# FPGA_SLM.net
KiCad netlist of a schematic drawn in Altium Designer
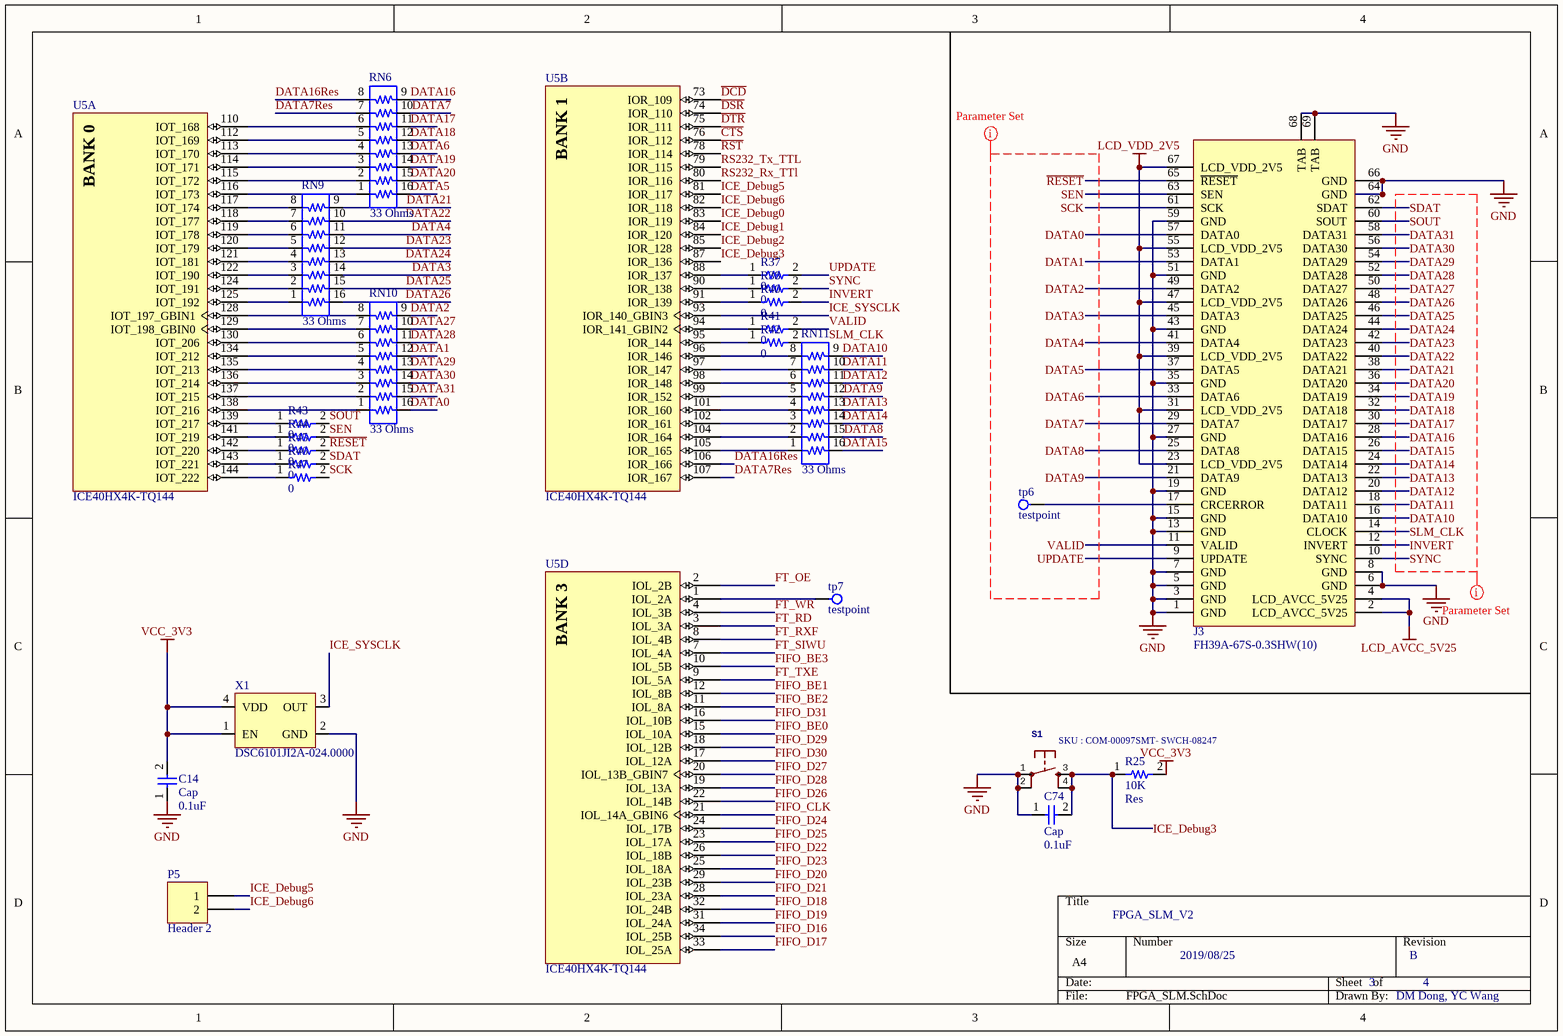
[diagram p0: FPGA_SLM.SchDoc]

(export (version "E")
  (design (tool "Eeschema 10.0.6"))
  (components
    (comp (ref "C14")
      (value "0.1uF")
      (footprint "Cap_0.1uF")
      (description "Multilayer Ceramic Capacitors MLCC - SMD/SMT 0.1uF 10% 50V AEC-Q200")
      (fields
        (field (name "COMPONENT NAME") "Cap")
        (field (name "Comment") "AC0603KRX7R9BB104")
        (field (name "CREATED BY") "Daoming Dong")
      )
      (libsource (lib "USB_FPGA_SLM_v1") (part "Cap_0.1uF"))
    )
    (comp (ref "C74")
      (value "0.1uF")
      (footprint "Cap_0.1uF")
      (description "Multilayer Ceramic Capacitors MLCC - SMD/SMT 0.1uF 10% 50V AEC-Q200")
      (fields
        (field (name "COMPONENT NAME") "Cap")
        (field (name "Comment") "AC0603KRX7R9BB104")
        (field (name "CREATED BY") "Daoming Dong")
      )
      (libsource (lib "USB_FPGA_SLM_v1") (part "Cap_0.1uF"))
    )
    (comp (ref "J3")
      (value "FH39A-67S-0.3SHW(10)")
      (footprint "Hirose_connector")
      (description "FFC & FPC Connectors FPC ZIF CONN 67 POS SMT HORZ MNT")
      (fields (field (name "CREATED BY") "Daoming Dong"))
      (libsource (lib "USB_FPGA_SLM_v1") (part "FH39A-67S-0.3SHW(10)"))
    )
    (comp (ref "P5")
      (value "Header 2")
      (footprint "HDR1X2")
      (description "Header, 2-Pin")
      (fields (field (name "PUBLISHER") "Altium Limited"))
      (libsource (lib "Miscellaneous Connectors") (part "Header 2"))
    )
    (comp (ref "R25")
      (value "10K")
      (footprint "RES_10K")
      (description "Thin Film Resistors - SMD 10K ohm 0.05% 50 ppm High-Precision")
      (fields
        (field (name "COMPONENT NAME") "Res")
        (field (name "Comment") "RT0603WRE0710KL")
        (field (name "CREATED BY") "Daoming Dong")
      )
      (libsource (lib "USB_FPGA_SLM_v1") (part "Res_10K"))
    )
    (comp (ref "R37")
      (value "0")
      (footprint "RES_0")
      (description "Thick Film Resistors - SMD 1/10Watt 0ohms Commercial Use")
      (fields (field (name "Comment") "CRCW06030000Z0EAC") (field (name "CREATED BY") "Daoming Dong"))
      (libsource (lib "USB_FPGA_SLM_v1") (part "Res_0"))
    )
    (comp (ref "R38")
      (value "0")
      (footprint "RES_0")
      (description "Thick Film Resistors - SMD 1/10Watt 0ohms Commercial Use")
      (fields (field (name "Comment") "CRCW06030000Z0EAC") (field (name "CREATED BY") "Daoming Dong"))
      (libsource (lib "USB_FPGA_SLM_v1") (part "Res_0"))
    )
    (comp (ref "R40")
      (value "0")
      (footprint "RES_0")
      (description "Thick Film Resistors - SMD 1/10Watt 0ohms Commercial Use")
      (fields (field (name "Comment") "CRCW06030000Z0EAC") (field (name "CREATED BY") "Daoming Dong"))
      (libsource (lib "USB_FPGA_SLM_v1") (part "Res_0"))
    )
    (comp (ref "R41")
      (value "0")
      (footprint "RES_0")
      (description "Thick Film Resistors - SMD 1/10Watt 0ohms Commercial Use")
      (fields (field (name "Comment") "CRCW06030000Z0EAC") (field (name "CREATED BY") "Daoming Dong"))
      (libsource (lib "USB_FPGA_SLM_v1") (part "Res_0"))
    )
    (comp (ref "R42")
      (value "0")
      (footprint "RES_0")
      (description "Thick Film Resistors - SMD 1/10Watt 0ohms Commercial Use")
      (fields (field (name "Comment") "CRCW06030000Z0EAC") (field (name "CREATED BY") "Daoming Dong"))
      (libsource (lib "USB_FPGA_SLM_v1") (part "Res_0"))
    )
    (comp (ref "R43")
      (value "0")
      (footprint "RES_0")
      (description "Thick Film Resistors - SMD 1/10Watt 0ohms Commercial Use")
      (fields (field (name "Comment") "CRCW06030000Z0EAC") (field (name "CREATED BY") "Daoming Dong"))
      (libsource (lib "USB_FPGA_SLM_v1") (part "Res_0"))
    )
    (comp (ref "R44")
      (value "0")
      (footprint "RES_0")
      (description "Thick Film Resistors - SMD 1/10Watt 0ohms Commercial Use")
      (fields (field (name "Comment") "CRCW06030000Z0EAC") (field (name "CREATED BY") "Daoming Dong"))
      (libsource (lib "USB_FPGA_SLM_v1") (part "Res_0"))
    )
    (comp (ref "R45")
      (value "0")
      (footprint "RES_0")
      (description "Thick Film Resistors - SMD 1/10Watt 0ohms Commercial Use")
      (fields (field (name "Comment") "CRCW06030000Z0EAC") (field (name "CREATED BY") "Daoming Dong"))
      (libsource (lib "USB_FPGA_SLM_v1") (part "Res_0"))
    )
    (comp (ref "R46")
      (value "0")
      (footprint "RES_0")
      (description "Thick Film Resistors - SMD 1/10Watt 0ohms Commercial Use")
      (fields (field (name "Comment") "CRCW06030000Z0EAC") (field (name "CREATED BY") "Daoming Dong"))
      (libsource (lib "USB_FPGA_SLM_v1") (part "Res_0"))
    )
    (comp (ref "R47")
      (value "0")
      (footprint "RES_0")
      (description "Thick Film Resistors - SMD 1/10Watt 0ohms Commercial Use")
      (fields (field (name "Comment") "CRCW06030000Z0EAC") (field (name "CREATED BY") "Daoming Dong"))
      (libsource (lib "USB_FPGA_SLM_v1") (part "Res_0"))
    )
    (comp (ref "RN6")
      (value "33 Ohms")
      (footprint "ResArray_0")
      (description "Resistor Networks & Arrays 33 OHM 5%")
      (fields (field (name "Comment") "EXB-2HV330JV"))
      (libsource (lib "USB_FPGA_SLM_v1") (part "ResArray"))
    )
    (comp (ref "RN9")
      (value "33 Ohms")
      (footprint "ResArray_0")
      (description "Resistor Networks & Arrays 33 OHM 5%")
      (fields (field (name "Comment") "EXB-2HV330JV"))
      (libsource (lib "USB_FPGA_SLM_v1") (part "ResArray"))
    )
    (comp (ref "RN10")
      (value "33 Ohms")
      (footprint "ResArray_0")
      (description "Resistor Networks & Arrays 33 OHM 5%")
      (fields (field (name "Comment") "EXB-2HV330JV"))
      (libsource (lib "USB_FPGA_SLM_v1") (part "ResArray"))
    )
    (comp (ref "RN11")
      (value "33 Ohms")
      (footprint "ResArray_0")
      (description "Resistor Networks & Arrays 33 OHM 5%")
      (fields (field (name "Comment") "EXB-2HV330JV"))
      (libsource (lib "USB_FPGA_SLM_v1") (part "ResArray"))
    )
    (comp (ref "S1")
      (value "SKU : COM-00097SMT- SWCH-08247")
      (footprint "TACTILE-PTH")
      (libsource (lib "SparkFun-Electromechanical") (part "TAC_SWITCHPTH"))
    )
    (comp (ref "tp6")
      (value "testpoint")
      (footprint "testpoint")
      (description "Testpoint for testing voltage")
      (fields (field (name "CREATED BY") "Daoming Dong"))
      (libsource (lib "USB_FPGA_SLM_v1") (part "Testpoint"))
    )
    (comp (ref "tp7")
      (value "testpoint")
      (footprint "testpoint")
      (description "Testpoint for testing voltage")
      (fields (field (name "CREATED BY") "Daoming Dong"))
      (libsource (lib "USB_FPGA_SLM_v1") (part "Testpoint"))
    )
    (comp (ref "U5")
      (value "ICE40HX4K-TQ144")
      (footprint "LATC-TQFP-144_L")
      (fields (field (name "MANUFACTURER") "Lattice Semiconductor"))
      (libsource (lib "Lattice iCE40") (part "ICE40HX4K-TQ144"))
    )
    (comp (ref "X1")
      (value "DSC6101JI2A-024.0000")
      (footprint "24MHzOscillator")
      (description "Standard Clock Oscillators MEMS Oscillator, Ultra Low Power, LVCMOS, -40C-85C, 25ppm, 2.5x2.0mm")
      (fields (field (name "CREATED BY") "Daoming Dong"))
      (libsource (lib "USB_FPGA_SLM_v1") (part "24MHzOscillator"))
    )
  )
  (nets
    (net (code "1") (name "/DATA0") (class "Default")
      (node (ref "J3") (pin "57") (pinfunction "DATA0_57") (pintype "passive"))
      (node (ref "RN10") (pin "16") (pinfunction "16_16") (pintype "passive"))
    )
    (net (code "2") (name "/DATA1") (class "Default")
      (node (ref "J3") (pin "53") (pinfunction "DATA1_53") (pintype "passive"))
      (node (ref "RN10") (pin "12") (pinfunction "12_12") (pintype "passive"))
    )
    (net (code "3") (name "/DATA2") (class "Default")
      (node (ref "J3") (pin "49") (pinfunction "DATA2_49") (pintype "passive"))
      (node (ref "RN10") (pin "9") (pinfunction "9_9") (pintype "passive"))
    )
    (net (code "4") (name "/DATA3") (class "Default")
      (node (ref "J3") (pin "45") (pinfunction "DATA3_45") (pintype "passive"))
      (node (ref "RN9") (pin "14") (pinfunction "14_14") (pintype "passive"))
    )
    (net (code "5") (name "/DATA4") (class "Default")
      (node (ref "J3") (pin "41") (pinfunction "DATA4_41") (pintype "passive"))
      (node (ref "RN9") (pin "11") (pinfunction "11_11") (pintype "passive"))
    )
    (net (code "6") (name "/DATA5") (class "Default")
      (node (ref "J3") (pin "37") (pinfunction "DATA5_37") (pintype "passive"))
      (node (ref "RN6") (pin "16") (pinfunction "16_16") (pintype "passive"))
    )
    (net (code "7") (name "/DATA6") (class "Default")
      (node (ref "J3") (pin "33") (pinfunction "DATA6_33") (pintype "passive"))
      (node (ref "RN6") (pin "13") (pinfunction "13_13") (pintype "passive"))
    )
    (net (code "8") (name "/DATA7") (class "Default")
      (node (ref "J3") (pin "29") (pinfunction "DATA7_29") (pintype "passive"))
      (node (ref "RN6") (pin "10") (pinfunction "10_10") (pintype "passive"))
    )
    (net (code "9") (name "/DATA7Res") (class "Default")
      (node (ref "RN6") (pin "7") (pinfunction "7_7") (pintype "passive"))
      (node (ref "U5") (pin "107") (pinfunction "IOR_167_107") (pintype "bidirectional"))
    )
    (net (code "10") (name "/DATA8") (class "Default")
      (node (ref "J3") (pin "25") (pinfunction "DATA8_25") (pintype "passive"))
      (node (ref "RN11") (pin "15") (pinfunction "15_15") (pintype "passive"))
    )
    (net (code "11") (name "/DATA9") (class "Default")
      (node (ref "J3") (pin "21") (pinfunction "DATA9_21") (pintype "passive"))
      (node (ref "RN11") (pin "12") (pinfunction "12_12") (pintype "passive"))
    )
    (net (code "12") (name "/DATA10") (class "Default")
      (node (ref "J3") (pin "16") (pinfunction "DATA10_16") (pintype "passive"))
      (node (ref "RN11") (pin "9") (pinfunction "9_9") (pintype "passive"))
    )
    (net (code "13") (name "/DATA11") (class "Default")
      (node (ref "J3") (pin "18") (pinfunction "DATA11_18") (pintype "passive"))
      (node (ref "RN11") (pin "10") (pinfunction "10_10") (pintype "passive"))
    )
    (net (code "14") (name "/DATA12") (class "Default")
      (node (ref "J3") (pin "20") (pinfunction "DATA12_20") (pintype "passive"))
      (node (ref "RN11") (pin "11") (pinfunction "11_11") (pintype "passive"))
    )
    (net (code "15") (name "/DATA13") (class "Default")
      (node (ref "J3") (pin "22") (pinfunction "DATA13_22") (pintype "passive"))
      (node (ref "RN11") (pin "13") (pinfunction "13_13") (pintype "passive"))
    )
    (net (code "16") (name "/DATA14") (class "Default")
      (node (ref "J3") (pin "24") (pinfunction "DATA14_24") (pintype "passive"))
      (node (ref "RN11") (pin "14") (pinfunction "14_14") (pintype "passive"))
    )
    (net (code "17") (name "/DATA15") (class "Default")
      (node (ref "J3") (pin "26") (pinfunction "DATA15_26") (pintype "passive"))
      (node (ref "RN11") (pin "16") (pinfunction "16_16") (pintype "passive"))
    )
    (net (code "18") (name "/DATA16") (class "Default")
      (node (ref "J3") (pin "28") (pinfunction "DATA16_28") (pintype "passive"))
      (node (ref "RN6") (pin "9") (pinfunction "9_9") (pintype "passive"))
    )
    (net (code "19") (name "/DATA16Res") (class "Default")
      (node (ref "RN6") (pin "8") (pinfunction "8_8") (pintype "passive"))
      (node (ref "U5") (pin "106") (pinfunction "IOR_166_106") (pintype "bidirectional"))
    )
    (net (code "20") (name "/DATA17") (class "Default")
      (node (ref "J3") (pin "30") (pinfunction "DATA17_30") (pintype "passive"))
      (node (ref "RN6") (pin "11") (pinfunction "11_11") (pintype "passive"))
    )
    (net (code "21") (name "/DATA18") (class "Default")
      (node (ref "J3") (pin "32") (pinfunction "DATA18_32") (pintype "passive"))
      (node (ref "RN6") (pin "12") (pinfunction "12_12") (pintype "passive"))
    )
    (net (code "22") (name "/DATA19") (class "Default")
      (node (ref "J3") (pin "34") (pinfunction "DATA19_34") (pintype "passive"))
      (node (ref "RN6") (pin "14") (pinfunction "14_14") (pintype "passive"))
    )
    (net (code "23") (name "/DATA20") (class "Default")
      (node (ref "J3") (pin "36") (pinfunction "DATA20_36") (pintype "passive"))
      (node (ref "RN6") (pin "15") (pinfunction "15_15") (pintype "passive"))
    )
    (net (code "24") (name "/DATA21") (class "Default")
      (node (ref "J3") (pin "38") (pinfunction "DATA21_38") (pintype "passive"))
      (node (ref "RN9") (pin "9") (pinfunction "9_9") (pintype "passive"))
    )
    (net (code "25") (name "/DATA22") (class "Default")
      (node (ref "J3") (pin "40") (pinfunction "DATA22_40") (pintype "passive"))
      (node (ref "RN9") (pin "10") (pinfunction "10_10") (pintype "passive"))
    )
    (net (code "26") (name "/DATA23") (class "Default")
      (node (ref "J3") (pin "42") (pinfunction "DATA23_42") (pintype "passive"))
      (node (ref "RN9") (pin "12") (pinfunction "12_12") (pintype "passive"))
    )
    (net (code "27") (name "/DATA24") (class "Default")
      (node (ref "J3") (pin "44") (pinfunction "DATA24_44") (pintype "passive"))
      (node (ref "RN9") (pin "13") (pinfunction "13_13") (pintype "passive"))
    )
    (net (code "28") (name "/DATA25") (class "Default")
      (node (ref "J3") (pin "46") (pinfunction "DATA25_46") (pintype "passive"))
      (node (ref "RN9") (pin "15") (pinfunction "15_15") (pintype "passive"))
    )
    (net (code "29") (name "/DATA26") (class "Default")
      (node (ref "J3") (pin "48") (pinfunction "DATA26_48") (pintype "passive"))
      (node (ref "RN9") (pin "16") (pinfunction "16_16") (pintype "passive"))
    )
    (net (code "30") (name "/DATA27") (class "Default")
      (node (ref "J3") (pin "50") (pinfunction "DATA27_50") (pintype "passive"))
      (node (ref "RN10") (pin "10") (pinfunction "10_10") (pintype "passive"))
    )
    (net (code "31") (name "/DATA28") (class "Default")
      (node (ref "J3") (pin "52") (pinfunction "DATA28_52") (pintype "passive"))
      (node (ref "RN10") (pin "11") (pinfunction "11_11") (pintype "passive"))
    )
    (net (code "32") (name "/DATA29") (class "Default")
      (node (ref "J3") (pin "54") (pinfunction "DATA29_54") (pintype "passive"))
      (node (ref "RN10") (pin "13") (pinfunction "13_13") (pintype "passive"))
    )
    (net (code "33") (name "/DATA30") (class "Default")
      (node (ref "J3") (pin "56") (pinfunction "DATA30_56") (pintype "passive"))
      (node (ref "RN10") (pin "14") (pinfunction "14_14") (pintype "passive"))
    )
    (net (code "34") (name "/DATA31") (class "Default")
      (node (ref "J3") (pin "58") (pinfunction "DATA31_58") (pintype "passive"))
      (node (ref "RN10") (pin "15") (pinfunction "15_15") (pintype "passive"))
    )
    (net (code "35") (name "/FIFO_BE0") (class "Default")
      (node (ref "U5") (pin "15") (pinfunction "IOL_10A_15") (pintype "bidirectional"))
    )
    (net (code "36") (name "/FIFO_BE1") (class "Default")
      (node (ref "U5") (pin "12") (pinfunction "IOL_8B_12") (pintype "bidirectional"))
    )
    (net (code "37") (name "/FIFO_BE2") (class "Default")
      (node (ref "U5") (pin "11") (pinfunction "IOL_8A_11") (pintype "bidirectional"))
    )
    (net (code "38") (name "/FIFO_BE3") (class "Default")
      (node (ref "U5") (pin "10") (pinfunction "IOL_5B_10") (pintype "bidirectional"))
    )
    (net (code "39") (name "/FIFO_CLK") (class "Default")
      (node (ref "U5") (pin "21") (pinfunction "IOL_14A_GBIN6_21") (pintype "bidirectional"))
    )
    (net (code "40") (name "/FIFO_D16") (class "Default")
      (node (ref "U5") (pin "34") (pinfunction "IOL_25B_34") (pintype "bidirectional"))
    )
    (net (code "41") (name "/FIFO_D17") (class "Default")
      (node (ref "U5") (pin "33") (pinfunction "IOL_25A_33") (pintype "bidirectional"))
    )
    (net (code "42") (name "/FIFO_D18") (class "Default")
      (node (ref "U5") (pin "32") (pinfunction "IOL_24B_32") (pintype "bidirectional"))
    )
    (net (code "43") (name "/FIFO_D19") (class "Default")
      (node (ref "U5") (pin "31") (pinfunction "IOL_24A_31") (pintype "bidirectional"))
    )
    (net (code "44") (name "/FIFO_D20") (class "Default")
      (node (ref "U5") (pin "29") (pinfunction "IOL_23B_29") (pintype "bidirectional"))
    )
    (net (code "45") (name "/FIFO_D21") (class "Default")
      (node (ref "U5") (pin "28") (pinfunction "IOL_23A_28") (pintype "bidirectional"))
    )
    (net (code "46") (name "/FIFO_D22") (class "Default")
      (node (ref "U5") (pin "26") (pinfunction "IOL_18B_26") (pintype "bidirectional"))
    )
    (net (code "47") (name "/FIFO_D23") (class "Default")
      (node (ref "U5") (pin "25") (pinfunction "IOL_18A_25") (pintype "bidirectional"))
    )
    (net (code "48") (name "/FIFO_D24") (class "Default")
      (node (ref "U5") (pin "24") (pinfunction "IOL_17B_24") (pintype "bidirectional"))
    )
    (net (code "49") (name "/FIFO_D25") (class "Default")
      (node (ref "U5") (pin "23") (pinfunction "IOL_17A_23") (pintype "bidirectional"))
    )
    (net (code "50") (name "/FIFO_D26") (class "Default")
      (node (ref "U5") (pin "22") (pinfunction "IOL_14B_22") (pintype "bidirectional"))
    )
    (net (code "51") (name "/FIFO_D27") (class "Default")
      (node (ref "U5") (pin "20") (pinfunction "IOL_13B_GBIN7_20") (pintype "bidirectional"))
    )
    (net (code "52") (name "/FIFO_D28") (class "Default")
      (node (ref "U5") (pin "19") (pinfunction "IOL_13A_19") (pintype "bidirectional"))
    )
    (net (code "53") (name "/FIFO_D29") (class "Default")
      (node (ref "U5") (pin "18") (pinfunction "IOL_12B_18") (pintype "bidirectional"))
    )
    (net (code "54") (name "/FIFO_D30") (class "Default")
      (node (ref "U5") (pin "17") (pinfunction "IOL_12A_17") (pintype "bidirectional"))
    )
    (net (code "55") (name "/FIFO_D31") (class "Default")
      (node (ref "U5") (pin "16") (pinfunction "IOL_10B_16") (pintype "bidirectional"))
    )
    (net (code "56") (name "/FT_OE") (class "Default")
      (node (ref "U5") (pin "2") (pinfunction "IOL_2B_2") (pintype "bidirectional"))
    )
    (net (code "57") (name "/FT_RD") (class "Default")
      (node (ref "U5") (pin "3") (pinfunction "IOL_3A_3") (pintype "bidirectional"))
    )
    (net (code "58") (name "/FT_RXF") (class "Default")
      (node (ref "U5") (pin "8") (pinfunction "IOL_4B_8") (pintype "bidirectional"))
    )
    (net (code "59") (name "/FT_SIWU") (class "Default")
      (node (ref "U5") (pin "7") (pinfunction "IOL_4A_7") (pintype "bidirectional"))
    )
    (net (code "60") (name "/FT_TXE") (class "Default")
      (node (ref "U5") (pin "9") (pinfunction "IOL_5A_9") (pintype "bidirectional"))
    )
    (net (code "61") (name "/FT_WR") (class "Default")
      (node (ref "U5") (pin "4") (pinfunction "IOL_3B_4") (pintype "bidirectional"))
    )
    (net (code "62") (name "/ICE_Debug0") (class "Default")
      (node (ref "U5") (pin "83") (pinfunction "IOR_119_83") (pintype "bidirectional"))
    )
    (net (code "63") (name "/ICE_Debug1") (class "Default")
      (node (ref "U5") (pin "84") (pinfunction "IOR_120_84") (pintype "bidirectional"))
    )
    (net (code "64") (name "/ICE_Debug2") (class "Default")
      (node (ref "U5") (pin "85") (pinfunction "IOR_128_85") (pintype "bidirectional"))
    )
    (net (code "65") (name "/ICE_Debug3") (class "Default")
      (node (ref "C74") (pin "2") (pinfunction "2_2") (pintype "passive"))
      (node (ref "R25") (pin "1") (pinfunction "1_1") (pintype "passive"))
      (node (ref "S1") (pin "3") (pinfunction "3_3") (pintype "passive"))
      (node (ref "S1") (pin "4") (pinfunction "4_4") (pintype "passive"))
      (node (ref "U5") (pin "87") (pinfunction "IOR_136_87") (pintype "bidirectional"))
    )
    (net (code "66") (name "/ICE_Debug5") (class "Default")
      (node (ref "P5") (pin "1") (pinfunction "1_1") (pintype "passive"))
      (node (ref "U5") (pin "81") (pinfunction "IOR_117_81") (pintype "bidirectional"))
    )
    (net (code "67") (name "/ICE_Debug6") (class "Default")
      (node (ref "P5") (pin "2") (pinfunction "2_2") (pintype "passive"))
      (node (ref "U5") (pin "82") (pinfunction "IOR_118_82") (pintype "bidirectional"))
    )
    (net (code "68") (name "/ICE_SYSCLK") (class "Default")
      (node (ref "U5") (pin "93") (pinfunction "IOR_140_GBIN3_93") (pintype "bidirectional"))
      (node (ref "X1") (pin "3") (pinfunction "OUT_3") (pintype "passive"))
    )
    (net (code "69") (name "/INVERT") (class "Default")
      (node (ref "J3") (pin "12") (pinfunction "INVERT_12") (pintype "passive"))
      (node (ref "R40") (pin "2") (pinfunction "2_2") (pintype "passive"))
    )
    (net (code "70") (name "/RS232_Rx_TTl") (class "Default")
      (node (ref "U5") (pin "80") (pinfunction "IOR_116_80") (pintype "bidirectional"))
    )
    (net (code "71") (name "/RS232_Tx_TTL") (class "Default")
      (node (ref "U5") (pin "79") (pinfunction "IOR_115_79") (pintype "bidirectional"))
    )
    (net (code "72") (name "/SCK") (class "Default")
      (node (ref "J3") (pin "61") (pinfunction "SCK_61") (pintype "passive"))
      (node (ref "R47") (pin "2") (pinfunction "2_2") (pintype "passive"))
    )
    (net (code "73") (name "/SDAT") (class "Default")
      (node (ref "J3") (pin "62") (pinfunction "SDAT_62") (pintype "passive"))
      (node (ref "R46") (pin "2") (pinfunction "2_2") (pintype "passive"))
    )
    (net (code "74") (name "/SEN") (class "Default")
      (node (ref "J3") (pin "63") (pinfunction "SEN_63") (pintype "passive"))
      (node (ref "R44") (pin "2") (pinfunction "2_2") (pintype "passive"))
    )
    (net (code "75") (name "/SLM_CLK") (class "Default")
      (node (ref "J3") (pin "14") (pinfunction "CLOCK_14") (pintype "passive"))
      (node (ref "R42") (pin "2") (pinfunction "2_2") (pintype "passive"))
    )
    (net (code "76") (name "/SOUT") (class "Default")
      (node (ref "J3") (pin "60") (pinfunction "SOUT_60") (pintype "passive"))
      (node (ref "R43") (pin "2") (pinfunction "2_2") (pintype "passive"))
    )
    (net (code "77") (name "/SYNC") (class "Default")
      (node (ref "J3") (pin "10") (pinfunction "SYNC_10") (pintype "passive"))
      (node (ref "R38") (pin "2") (pinfunction "2_2") (pintype "passive"))
    )
    (net (code "78") (name "/UPDATE") (class "Default")
      (node (ref "J3") (pin "9") (pinfunction "UPDATE_9") (pintype "passive"))
      (node (ref "R37") (pin "2") (pinfunction "2_2") (pintype "passive"))
    )
    (net (code "79") (name "/VALID") (class "Default")
      (node (ref "J3") (pin "11") (pinfunction "VALID_11") (pintype "passive"))
      (node (ref "R41") (pin "2") (pinfunction "2_2") (pintype "passive"))
    )
    (net (code "80") (name "/~{CTS}") (class "Default")
      (node (ref "U5") (pin "76") (pinfunction "IOR_112_76") (pintype "bidirectional"))
    )
    (net (code "81") (name "/~{DCD}") (class "Default")
      (node (ref "U5") (pin "73") (pinfunction "IOR_109_73") (pintype "bidirectional"))
    )
    (net (code "82") (name "/~{DSR}") (class "Default")
      (node (ref "U5") (pin "74") (pinfunction "IOR_110_74") (pintype "bidirectional"))
    )
    (net (code "83") (name "/~{DTR}") (class "Default")
      (node (ref "U5") (pin "75") (pinfunction "IOR_111_75") (pintype "bidirectional"))
    )
    (net (code "84") (name "/~{RESET}") (class "Default")
      (node (ref "J3") (pin "65") (pinfunction "~{RESET}_65") (pintype "passive"))
      (node (ref "R45") (pin "2") (pinfunction "2_2") (pintype "passive"))
    )
    (net (code "85") (name "/~{RST}") (class "Default")
      (node (ref "U5") (pin "78") (pinfunction "IOR_114_78") (pintype "bidirectional"))
    )
    (net (code "86") (name "GND") (class "Default")
      (node (ref "C14") (pin "1") (pinfunction "1_1") (pintype "passive"))
      (node (ref "C74") (pin "1") (pinfunction "1_1") (pintype "passive"))
      (node (ref "J3") (pin "1") (pinfunction "GND_1") (pintype "passive"))
      (node (ref "J3") (pin "13") (pinfunction "GND_13") (pintype "passive"))
      (node (ref "J3") (pin "15") (pinfunction "GND_15") (pintype "passive"))
      (node (ref "J3") (pin "19") (pinfunction "GND_19") (pintype "passive"))
      (node (ref "J3") (pin "27") (pinfunction "GND_27") (pintype "passive"))
      (node (ref "J3") (pin "3") (pinfunction "GND_3") (pintype "passive"))
      (node (ref "J3") (pin "35") (pinfunction "GND_35") (pintype "passive"))
      (node (ref "J3") (pin "43") (pinfunction "GND_43") (pintype "passive"))
      (node (ref "J3") (pin "5") (pinfunction "GND_5") (pintype "passive"))
      (node (ref "J3") (pin "51") (pinfunction "GND_51") (pintype "passive"))
      (node (ref "J3") (pin "59") (pinfunction "GND_59") (pintype "passive"))
      (node (ref "J3") (pin "6") (pinfunction "GND_6") (pintype "passive"))
      (node (ref "J3") (pin "64") (pinfunction "GND_64") (pintype "passive"))
      (node (ref "J3") (pin "66") (pinfunction "GND_66") (pintype "passive"))
      (node (ref "J3") (pin "68") (pinfunction "TAB_68") (pintype "passive"))
      (node (ref "J3") (pin "69") (pinfunction "TAB_69") (pintype "passive"))
      (node (ref "J3") (pin "7") (pinfunction "GND_7") (pintype "passive"))
      (node (ref "J3") (pin "8") (pinfunction "GND_8") (pintype "passive"))
      (node (ref "S1") (pin "1") (pinfunction "1_1") (pintype "passive"))
      (node (ref "S1") (pin "2") (pinfunction "2_2") (pintype "passive"))
      (node (ref "X1") (pin "2") (pinfunction "GND_2") (pintype "passive"))
    )
    (net (code "87") (name "LCD_AVCC_5V25") (class "Default")
      (node (ref "J3") (pin "2") (pinfunction "LCD_AVCC_5V25_2") (pintype "passive"))
      (node (ref "J3") (pin "4") (pinfunction "LCD_AVCC_5V25_4") (pintype "passive"))
    )
    (net (code "88") (name "LCD_VDD_2V5") (class "Default")
      (node (ref "J3") (pin "23") (pinfunction "LCD_VDD_2V5_23") (pintype "passive"))
      (node (ref "J3") (pin "31") (pinfunction "LCD_VDD_2V5_31") (pintype "passive"))
      (node (ref "J3") (pin "39") (pinfunction "LCD_VDD_2V5_39") (pintype "passive"))
      (node (ref "J3") (pin "47") (pinfunction "LCD_VDD_2V5_47") (pintype "passive"))
      (node (ref "J3") (pin "55") (pinfunction "LCD_VDD_2V5_55") (pintype "passive"))
      (node (ref "J3") (pin "67") (pinfunction "LCD_VDD_2V5_67") (pintype "passive"))
    )
    (net (code "89") (name "Net-(J3-CRCERROR)") (class "Default")
      (node (ref "J3") (pin "17") (pinfunction "CRCERROR_17") (pintype "passive"))
      (node (ref "tp6") (pin "1") (pinfunction "1_1") (pintype "passive"))
    )
    (net (code "90") (name "Net-(U5A-IOT_168)") (class "Default")
      (node (ref "RN6") (pin "6") (pinfunction "6_6") (pintype "passive"))
      (node (ref "U5") (pin "110") (pinfunction "IOT_168_110") (pintype "bidirectional"))
    )
    (net (code "91") (name "Net-(U5A-IOT_169)") (class "Default")
      (node (ref "RN6") (pin "5") (pinfunction "5_5") (pintype "passive"))
      (node (ref "U5") (pin "112") (pinfunction "IOT_169_112") (pintype "bidirectional"))
    )
    (net (code "92") (name "Net-(U5A-IOT_170)") (class "Default")
      (node (ref "RN6") (pin "4") (pinfunction "4_4") (pintype "passive"))
      (node (ref "U5") (pin "113") (pinfunction "IOT_170_113") (pintype "bidirectional"))
    )
    (net (code "93") (name "Net-(U5A-IOT_171)") (class "Default")
      (node (ref "RN6") (pin "3") (pinfunction "3_3") (pintype "passive"))
      (node (ref "U5") (pin "114") (pinfunction "IOT_171_114") (pintype "bidirectional"))
    )
    (net (code "94") (name "Net-(U5A-IOT_172)") (class "Default")
      (node (ref "RN6") (pin "2") (pinfunction "2_2") (pintype "passive"))
      (node (ref "U5") (pin "115") (pinfunction "IOT_172_115") (pintype "bidirectional"))
    )
    (net (code "95") (name "Net-(U5A-IOT_173)") (class "Default")
      (node (ref "RN6") (pin "1") (pinfunction "1_1") (pintype "passive"))
      (node (ref "U5") (pin "116") (pinfunction "IOT_173_116") (pintype "bidirectional"))
    )
    (net (code "96") (name "Net-(U5A-IOT_174)") (class "Default")
      (node (ref "RN9") (pin "8") (pinfunction "8_8") (pintype "passive"))
      (node (ref "U5") (pin "117") (pinfunction "IOT_174_117") (pintype "bidirectional"))
    )
    (net (code "97") (name "Net-(U5A-IOT_177)") (class "Default")
      (node (ref "RN9") (pin "7") (pinfunction "7_7") (pintype "passive"))
      (node (ref "U5") (pin "118") (pinfunction "IOT_177_118") (pintype "bidirectional"))
    )
    (net (code "98") (name "Net-(U5A-IOT_178)") (class "Default")
      (node (ref "RN9") (pin "6") (pinfunction "6_6") (pintype "passive"))
      (node (ref "U5") (pin "119") (pinfunction "IOT_178_119") (pintype "bidirectional"))
    )
    (net (code "99") (name "Net-(U5A-IOT_179)") (class "Default")
      (node (ref "RN9") (pin "5") (pinfunction "5_5") (pintype "passive"))
      (node (ref "U5") (pin "120") (pinfunction "IOT_179_120") (pintype "bidirectional"))
    )
    (net (code "100") (name "Net-(U5A-IOT_181)") (class "Default")
      (node (ref "RN9") (pin "4") (pinfunction "4_4") (pintype "passive"))
      (node (ref "U5") (pin "121") (pinfunction "IOT_181_121") (pintype "bidirectional"))
    )
    (net (code "101") (name "Net-(U5A-IOT_190)") (class "Default")
      (node (ref "RN9") (pin "3") (pinfunction "3_3") (pintype "passive"))
      (node (ref "U5") (pin "122") (pinfunction "IOT_190_122") (pintype "bidirectional"))
    )
    (net (code "102") (name "Net-(U5A-IOT_191)") (class "Default")
      (node (ref "RN9") (pin "2") (pinfunction "2_2") (pintype "passive"))
      (node (ref "U5") (pin "124") (pinfunction "IOT_191_124") (pintype "bidirectional"))
    )
    (net (code "103") (name "Net-(U5A-IOT_192)") (class "Default")
      (node (ref "RN9") (pin "1") (pinfunction "1_1") (pintype "passive"))
      (node (ref "U5") (pin "125") (pinfunction "IOT_192_125") (pintype "bidirectional"))
    )
    (net (code "104") (name "Net-(U5A-IOT_197_GBIN1)") (class "Default")
      (node (ref "RN10") (pin "8") (pinfunction "8_8") (pintype "passive"))
      (node (ref "U5") (pin "128") (pinfunction "IOT_197_GBIN1_128") (pintype "bidirectional"))
    )
    (net (code "105") (name "Net-(U5A-IOT_198_GBIN0)") (class "Default")
      (node (ref "RN10") (pin "7") (pinfunction "7_7") (pintype "passive"))
      (node (ref "U5") (pin "129") (pinfunction "IOT_198_GBIN0_129") (pintype "bidirectional"))
    )
    (net (code "106") (name "Net-(U5A-IOT_206)") (class "Default")
      (node (ref "RN10") (pin "6") (pinfunction "6_6") (pintype "passive"))
      (node (ref "U5") (pin "130") (pinfunction "IOT_206_130") (pintype "bidirectional"))
    )
    (net (code "107") (name "Net-(U5A-IOT_212)") (class "Default")
      (node (ref "RN10") (pin "5") (pinfunction "5_5") (pintype "passive"))
      (node (ref "U5") (pin "134") (pinfunction "IOT_212_134") (pintype "bidirectional"))
    )
    (net (code "108") (name "Net-(U5A-IOT_213)") (class "Default")
      (node (ref "RN10") (pin "4") (pinfunction "4_4") (pintype "passive"))
      (node (ref "U5") (pin "135") (pinfunction "IOT_213_135") (pintype "bidirectional"))
    )
    (net (code "109") (name "Net-(U5A-IOT_214)") (class "Default")
      (node (ref "RN10") (pin "3") (pinfunction "3_3") (pintype "passive"))
      (node (ref "U5") (pin "136") (pinfunction "IOT_214_136") (pintype "bidirectional"))
    )
    (net (code "110") (name "Net-(U5A-IOT_215)") (class "Default")
      (node (ref "RN10") (pin "2") (pinfunction "2_2") (pintype "passive"))
      (node (ref "U5") (pin "137") (pinfunction "IOT_215_137") (pintype "bidirectional"))
    )
    (net (code "111") (name "Net-(U5A-IOT_216)") (class "Default")
      (node (ref "RN10") (pin "1") (pinfunction "1_1") (pintype "passive"))
      (node (ref "U5") (pin "138") (pinfunction "IOT_216_138") (pintype "bidirectional"))
    )
    (net (code "112") (name "Net-(U5A-IOT_217)") (class "Default")
      (node (ref "R43") (pin "1") (pinfunction "1_1") (pintype "passive"))
      (node (ref "U5") (pin "139") (pinfunction "IOT_217_139") (pintype "bidirectional"))
    )
    (net (code "113") (name "Net-(U5A-IOT_219)") (class "Default")
      (node (ref "R44") (pin "1") (pinfunction "1_1") (pintype "passive"))
      (node (ref "U5") (pin "141") (pinfunction "IOT_219_141") (pintype "bidirectional"))
    )
    (net (code "114") (name "Net-(U5A-IOT_220)") (class "Default")
      (node (ref "R45") (pin "1") (pinfunction "1_1") (pintype "passive"))
      (node (ref "U5") (pin "142") (pinfunction "IOT_220_142") (pintype "bidirectional"))
    )
    (net (code "115") (name "Net-(U5A-IOT_221)") (class "Default")
      (node (ref "R46") (pin "1") (pinfunction "1_1") (pintype "passive"))
      (node (ref "U5") (pin "143") (pinfunction "IOT_221_143") (pintype "bidirectional"))
    )
    (net (code "116") (name "Net-(U5A-IOT_222)") (class "Default")
      (node (ref "R47") (pin "1") (pinfunction "1_1") (pintype "passive"))
      (node (ref "U5") (pin "144") (pinfunction "IOT_222_144") (pintype "bidirectional"))
    )
    (net (code "117") (name "Net-(U5B-IOR_137)") (class "Default")
      (node (ref "R37") (pin "1") (pinfunction "1_1") (pintype "passive"))
      (node (ref "U5") (pin "88") (pinfunction "IOR_137_88") (pintype "bidirectional"))
    )
    (net (code "118") (name "Net-(U5B-IOR_138)") (class "Default")
      (node (ref "R38") (pin "1") (pinfunction "1_1") (pintype "passive"))
      (node (ref "U5") (pin "90") (pinfunction "IOR_138_90") (pintype "bidirectional"))
    )
    (net (code "119") (name "Net-(U5B-IOR_139)") (class "Default")
      (node (ref "R40") (pin "1") (pinfunction "1_1") (pintype "passive"))
      (node (ref "U5") (pin "91") (pinfunction "IOR_139_91") (pintype "bidirectional"))
    )
    (net (code "120") (name "Net-(U5B-IOR_141_GBIN2)") (class "Default")
      (node (ref "R41") (pin "1") (pinfunction "1_1") (pintype "passive"))
      (node (ref "U5") (pin "94") (pinfunction "IOR_141_GBIN2_94") (pintype "bidirectional"))
    )
    (net (code "121") (name "Net-(U5B-IOR_144)") (class "Default")
      (node (ref "R42") (pin "1") (pinfunction "1_1") (pintype "passive"))
      (node (ref "U5") (pin "95") (pinfunction "IOR_144_95") (pintype "bidirectional"))
    )
    (net (code "122") (name "Net-(U5B-IOR_146)") (class "Default")
      (node (ref "RN11") (pin "8") (pinfunction "8_8") (pintype "passive"))
      (node (ref "U5") (pin "96") (pinfunction "IOR_146_96") (pintype "bidirectional"))
    )
    (net (code "123") (name "Net-(U5B-IOR_147)") (class "Default")
      (node (ref "RN11") (pin "7") (pinfunction "7_7") (pintype "passive"))
      (node (ref "U5") (pin "97") (pinfunction "IOR_147_97") (pintype "bidirectional"))
    )
    (net (code "124") (name "Net-(U5B-IOR_148)") (class "Default")
      (node (ref "RN11") (pin "6") (pinfunction "6_6") (pintype "passive"))
      (node (ref "U5") (pin "98") (pinfunction "IOR_148_98") (pintype "bidirectional"))
    )
    (net (code "125") (name "Net-(U5B-IOR_152)") (class "Default")
      (node (ref "RN11") (pin "5") (pinfunction "5_5") (pintype "passive"))
      (node (ref "U5") (pin "99") (pinfunction "IOR_152_99") (pintype "bidirectional"))
    )
    (net (code "126") (name "Net-(U5B-IOR_160)") (class "Default")
      (node (ref "RN11") (pin "4") (pinfunction "4_4") (pintype "passive"))
      (node (ref "U5") (pin "101") (pinfunction "IOR_160_101") (pintype "bidirectional"))
    )
    (net (code "127") (name "Net-(U5B-IOR_161)") (class "Default")
      (node (ref "RN11") (pin "3") (pinfunction "3_3") (pintype "passive"))
      (node (ref "U5") (pin "102") (pinfunction "IOR_161_102") (pintype "bidirectional"))
    )
    (net (code "128") (name "Net-(U5B-IOR_164)") (class "Default")
      (node (ref "RN11") (pin "2") (pinfunction "2_2") (pintype "passive"))
      (node (ref "U5") (pin "104") (pinfunction "IOR_164_104") (pintype "bidirectional"))
    )
    (net (code "129") (name "Net-(U5B-IOR_165)") (class "Default")
      (node (ref "RN11") (pin "1") (pinfunction "1_1") (pintype "passive"))
      (node (ref "U5") (pin "105") (pinfunction "IOR_165_105") (pintype "bidirectional"))
    )
    (net (code "130") (name "Net-(U5D-IOL_2A)") (class "Default")
      (node (ref "U5") (pin "1") (pinfunction "IOL_2A_1") (pintype "bidirectional"))
      (node (ref "tp7") (pin "1") (pinfunction "1_1") (pintype "passive"))
    )
    (net (code "131") (name "VCC_3V3") (class "Default")
      (node (ref "C14") (pin "2") (pinfunction "2_2") (pintype "passive"))
      (node (ref "R25") (pin "2") (pinfunction "2_2") (pintype "passive"))
      (node (ref "X1") (pin "1") (pinfunction "EN_1") (pintype "passive"))
      (node (ref "X1") (pin "4") (pinfunction "VDD_4") (pintype "passive"))
    )
  )
)
